# piano.net
KiCad netlist of a schematic drawn in EAGLE
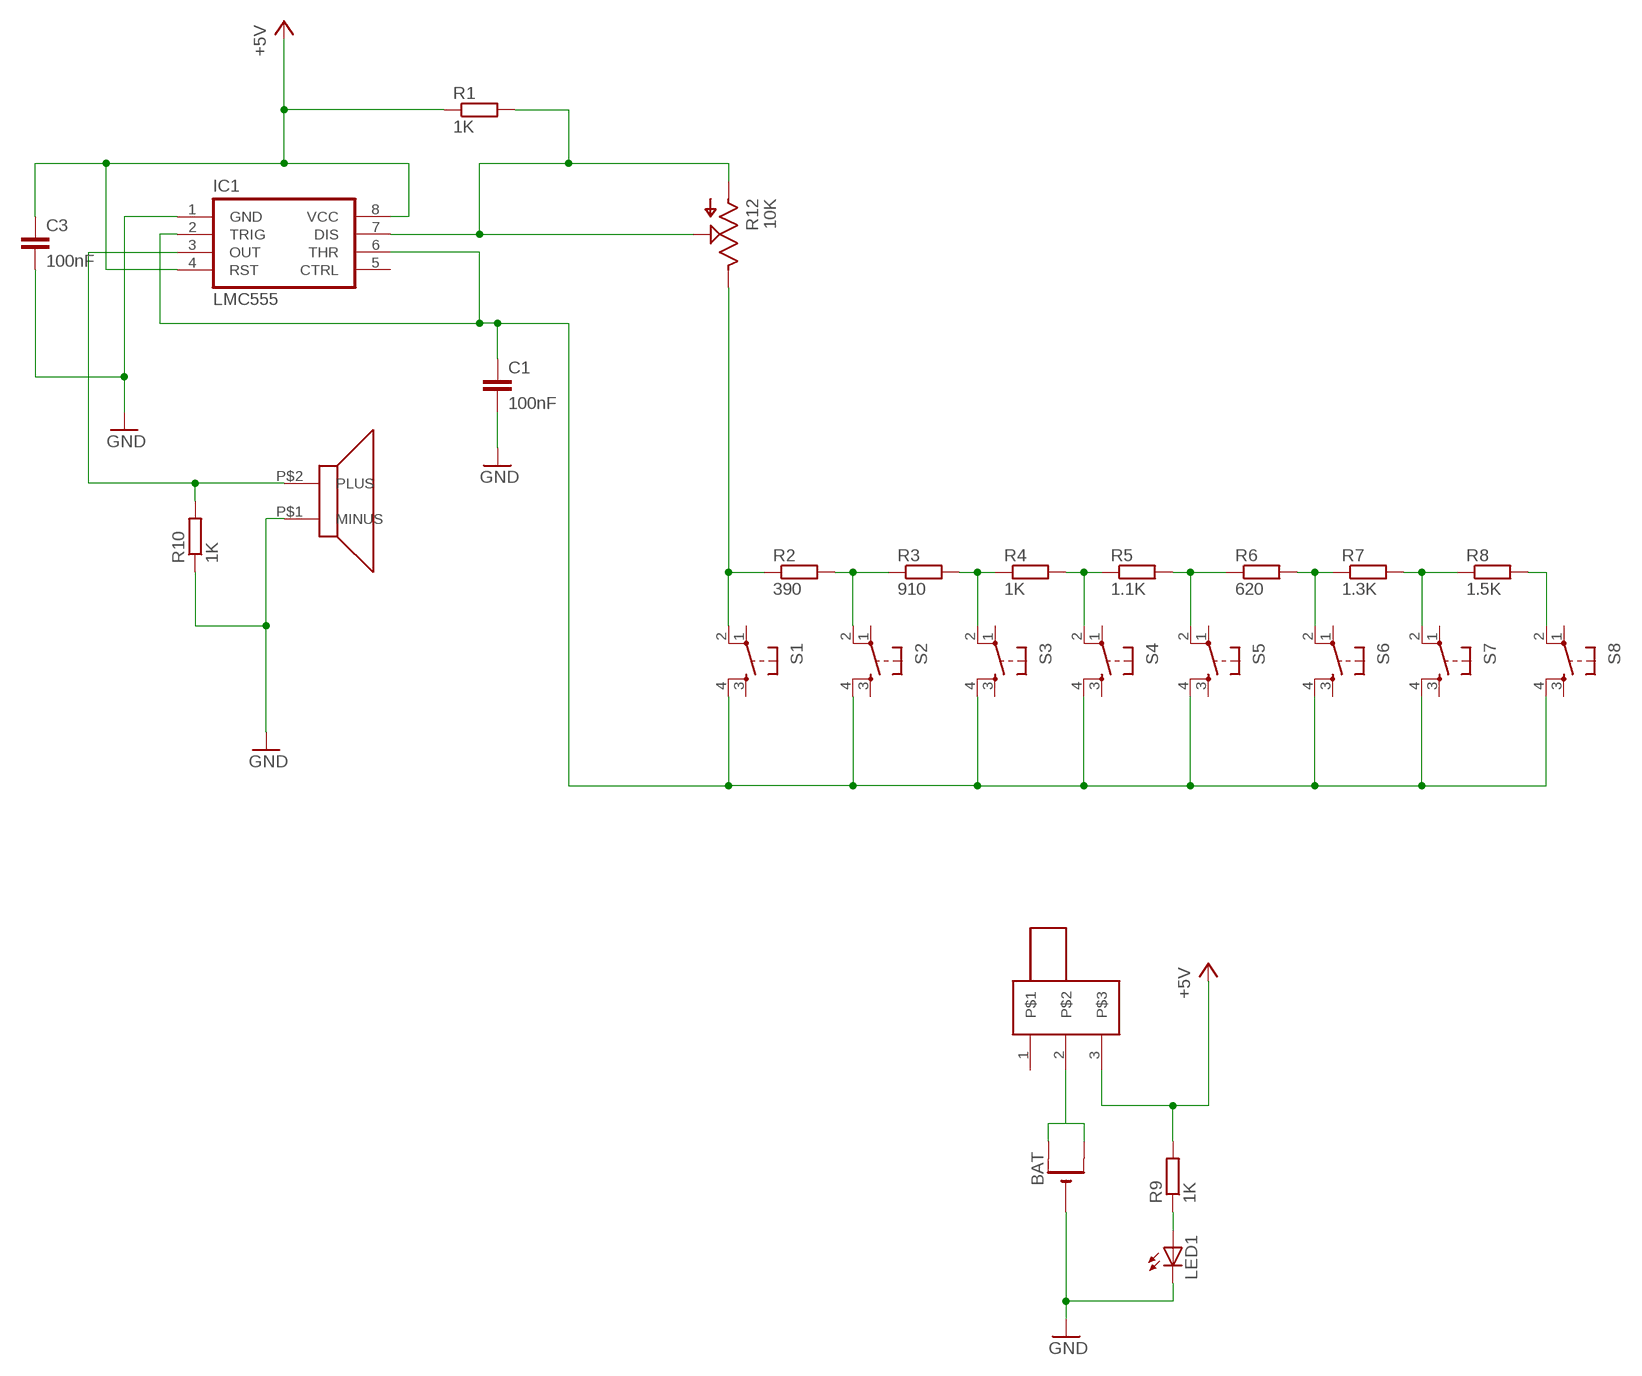
[diagram p0: schematic, sheet 1]

(export (version "E")
  (design (tool "Eeschema 10.0.6"))
  (components
    (comp (ref "BAT")
      (value "CR1220SMT")
      (footprint "eagle-import:CR1220-SMD")
      (libsource (lib "eagle-import") (part "CR1220SMT"))
    )
    (comp (ref "C1")
      (value "100nF")
      (footprint "eagle-import:C1206")
      (libsource (lib "eagle-import") (part "C-EUC1206"))
    )
    (comp (ref "C3")
      (value "100nF")
      (footprint "eagle-import:C1206")
      (libsource (lib "eagle-import") (part "C-EUC1206"))
    )
    (comp (ref "IC1")
      (value "LMC555")
      (footprint "eagle-import:SOIC-8")
      (libsource (lib "eagle-import") (part "IC_555-SOIC8"))
    )
    (comp (ref "LED1")
      (value "LED1206")
      (footprint "eagle-import:LED-1206")
      (libsource (lib "eagle-import") (part "LED1206"))
    )
    (comp (ref "R1")
      (value "1K")
      (footprint "eagle-import:R1206")
      (libsource (lib "eagle-import") (part "R-EU_R1206"))
    )
    (comp (ref "R2")
      (value "390")
      (footprint "eagle-import:R1206")
      (libsource (lib "eagle-import") (part "R-EU_R1206"))
    )
    (comp (ref "R3")
      (value "910")
      (footprint "eagle-import:R1206")
      (libsource (lib "eagle-import") (part "R-EU_R1206"))
    )
    (comp (ref "R4")
      (value "1K")
      (footprint "eagle-import:R1206")
      (libsource (lib "eagle-import") (part "R-EU_R1206"))
    )
    (comp (ref "R5")
      (value "1.1K")
      (footprint "eagle-import:R1206")
      (libsource (lib "eagle-import") (part "R-EU_R1206"))
    )
    (comp (ref "R6")
      (value "620")
      (footprint "eagle-import:R1206")
      (libsource (lib "eagle-import") (part "R-EU_R1206"))
    )
    (comp (ref "R7")
      (value "1.3K")
      (footprint "eagle-import:R1206")
      (libsource (lib "eagle-import") (part "R-EU_R1206"))
    )
    (comp (ref "R8")
      (value "1.5K")
      (footprint "eagle-import:R1206")
      (libsource (lib "eagle-import") (part "R-EU_R1206"))
    )
    (comp (ref "R9")
      (value "1K")
      (footprint "eagle-import:R1206")
      (libsource (lib "eagle-import") (part "R-EU_R1206"))
    )
    (comp (ref "R10")
      (value "1K")
      (footprint "eagle-import:R1206")
      (libsource (lib "eagle-import") (part "R-EU_R1206"))
    )
    (comp (ref "R12")
      (value "10K")
      (footprint "eagle-import:PVZ3A")
      (libsource (lib "eagle-import") (part "PVZ3A"))
    )
    (comp (ref "S1")
      (value "TAC_SWITCHSMD")
      (footprint "eagle-import:TACTILE_SWITCH_SMD")
      (libsource (lib "eagle-import") (part "TAC_SWITCHSMD"))
    )
    (comp (ref "S2")
      (value "TAC_SWITCHSMD")
      (footprint "eagle-import:TACTILE_SWITCH_SMD")
      (libsource (lib "eagle-import") (part "TAC_SWITCHSMD"))
    )
    (comp (ref "S3")
      (value "TAC_SWITCHSMD")
      (footprint "eagle-import:TACTILE_SWITCH_SMD")
      (libsource (lib "eagle-import") (part "TAC_SWITCHSMD"))
    )
    (comp (ref "S4")
      (value "TAC_SWITCHSMD")
      (footprint "eagle-import:TACTILE_SWITCH_SMD")
      (libsource (lib "eagle-import") (part "TAC_SWITCHSMD"))
    )
    (comp (ref "S5")
      (value "TAC_SWITCHSMD")
      (footprint "eagle-import:TACTILE_SWITCH_SMD")
      (libsource (lib "eagle-import") (part "TAC_SWITCHSMD"))
    )
    (comp (ref "S6")
      (value "TAC_SWITCHSMD")
      (footprint "eagle-import:TACTILE_SWITCH_SMD")
      (libsource (lib "eagle-import") (part "TAC_SWITCHSMD"))
    )
    (comp (ref "S7")
      (value "TAC_SWITCHSMD")
      (footprint "eagle-import:TACTILE_SWITCH_SMD")
      (libsource (lib "eagle-import") (part "TAC_SWITCHSMD"))
    )
    (comp (ref "S8")
      (value "TAC_SWITCHSMD")
      (footprint "eagle-import:TACTILE_SWITCH_SMD")
      (libsource (lib "eagle-import") (part "TAC_SWITCHSMD"))
    )
    (comp (ref "U$1")
      (value "SMD-100030H-05052T")
      (footprint "eagle-import:SMD-100030H")
      (libsource (lib "eagle-import") (part "SMD-100030H-05052T"))
    )
    (comp (ref "U$2")
      (value "SK12D07VG3")
      (footprint "eagle-import:SWITCH3")
      (libsource (lib "eagle-import") (part "SWITCH3"))
    )
  )
  (nets
    (net (code "1") (name "+5V") (class "Default")
      (node (ref "C3") (pin "1") (pinfunction "1_1") (pintype "passive"))
      (node (ref "IC1") (pin "4") (pinfunction "RST_4") (pintype "input"))
      (node (ref "IC1") (pin "8") (pinfunction "VCC_8") (pintype "power_in"))
      (node (ref "R1") (pin "1") (pinfunction "1_1") (pintype "passive"))
      (node (ref "R9") (pin "2") (pinfunction "2_2") (pintype "passive"))
      (node (ref "U$2") (pin "3") (pinfunction "P$3_3") (pintype "bidirectional"))
    )
    (net (code "2") (name "/CTRL") (class "Default")
      (node (ref "IC1") (pin "5") (pinfunction "CTRL_5") (pintype "power_in"))
    )
    (net (code "3") (name "GND") (class "Default")
      (node (ref "BAT") (pin "-") (pinfunction "-_-") (pintype "passive"))
      (node (ref "C1") (pin "2") (pinfunction "2_2") (pintype "passive"))
      (node (ref "C3") (pin "2") (pinfunction "2_2") (pintype "passive"))
      (node (ref "IC1") (pin "1") (pinfunction "GND_1") (pintype "power_in"))
      (node (ref "LED1") (pin "C") (pinfunction "C_C") (pintype "passive"))
      (node (ref "R10") (pin "1") (pinfunction "1_1") (pintype "passive"))
      (node (ref "U$1") (pin "P$1") (pinfunction "MINUS_P$1") (pintype "bidirectional"))
    )
    (net (code "4") (name "Net-(BAT-+)") (class "Default")
      (node (ref "BAT") (pin "+$1") (pinfunction "+_+$1") (pintype "passive"))
      (node (ref "BAT") (pin "+$2") (pinfunction "+1_+$2") (pintype "passive"))
      (node (ref "U$2") (pin "2") (pinfunction "P$2_2") (pintype "bidirectional"))
    )
    (net (code "5") (name "Net-(IC1-DIS)") (class "Default")
      (node (ref "IC1") (pin "7") (pinfunction "DIS_7") (pintype "input"))
      (node (ref "R1") (pin "2") (pinfunction "2_2") (pintype "passive"))
      (node (ref "R12") (pin "P$1") (pinfunction "P$1_P$1") (pintype "bidirectional"))
      (node (ref "R12") (pin "P$2") (pinfunction "P$2_P$2") (pintype "bidirectional"))
    )
    (net (code "6") (name "Net-(IC1-OUT)") (class "Default")
      (node (ref "IC1") (pin "3") (pinfunction "OUT_3") (pintype "output"))
      (node (ref "R10") (pin "2") (pinfunction "2_2") (pintype "passive"))
      (node (ref "U$1") (pin "P$2") (pinfunction "PLUS_P$2") (pintype "bidirectional"))
    )
    (net (code "7") (name "Net-(IC1-THR)") (class "Default")
      (node (ref "C1") (pin "1") (pinfunction "1_1") (pintype "passive"))
      (node (ref "IC1") (pin "2") (pinfunction "TRIG_2") (pintype "input"))
      (node (ref "IC1") (pin "6") (pinfunction "THR_6") (pintype "input"))
      (node (ref "S1") (pin "4") (pinfunction "4_4") (pintype "passive"))
      (node (ref "S2") (pin "4") (pinfunction "4_4") (pintype "passive"))
      (node (ref "S3") (pin "4") (pinfunction "4_4") (pintype "passive"))
      (node (ref "S4") (pin "4") (pinfunction "4_4") (pintype "passive"))
      (node (ref "S5") (pin "4") (pinfunction "4_4") (pintype "passive"))
      (node (ref "S6") (pin "4") (pinfunction "4_4") (pintype "passive"))
      (node (ref "S7") (pin "4") (pinfunction "4_4") (pintype "passive"))
      (node (ref "S8") (pin "4") (pinfunction "4_4") (pintype "passive"))
    )
    (net (code "8") (name "Net-(LED1-PadA)") (class "Default")
      (node (ref "LED1") (pin "A") (pinfunction "A_A") (pintype "passive"))
      (node (ref "R9") (pin "1") (pinfunction "1_1") (pintype "passive"))
    )
    (net (code "9") (name "Net-(R2-Pad2)") (class "Default")
      (node (ref "R2") (pin "2") (pinfunction "2_2") (pintype "passive"))
      (node (ref "R3") (pin "1") (pinfunction "1_1") (pintype "passive"))
      (node (ref "S2") (pin "2") (pinfunction "2_2") (pintype "passive"))
    )
    (net (code "10") (name "Net-(R3-Pad2)") (class "Default")
      (node (ref "R3") (pin "2") (pinfunction "2_2") (pintype "passive"))
      (node (ref "R4") (pin "1") (pinfunction "1_1") (pintype "passive"))
      (node (ref "S3") (pin "2") (pinfunction "2_2") (pintype "passive"))
    )
    (net (code "11") (name "Net-(R4-Pad2)") (class "Default")
      (node (ref "R4") (pin "2") (pinfunction "2_2") (pintype "passive"))
      (node (ref "R5") (pin "1") (pinfunction "1_1") (pintype "passive"))
      (node (ref "S4") (pin "2") (pinfunction "2_2") (pintype "passive"))
    )
    (net (code "12") (name "Net-(R5-Pad2)") (class "Default")
      (node (ref "R5") (pin "2") (pinfunction "2_2") (pintype "passive"))
      (node (ref "R6") (pin "1") (pinfunction "1_1") (pintype "passive"))
      (node (ref "S5") (pin "2") (pinfunction "2_2") (pintype "passive"))
    )
    (net (code "13") (name "Net-(R6-Pad2)") (class "Default")
      (node (ref "R6") (pin "2") (pinfunction "2_2") (pintype "passive"))
      (node (ref "R7") (pin "1") (pinfunction "1_1") (pintype "passive"))
      (node (ref "S6") (pin "2") (pinfunction "2_2") (pintype "passive"))
    )
    (net (code "14") (name "Net-(R7-Pad2)") (class "Default")
      (node (ref "R7") (pin "2") (pinfunction "2_2") (pintype "passive"))
      (node (ref "R8") (pin "1") (pinfunction "1_1") (pintype "passive"))
      (node (ref "S7") (pin "2") (pinfunction "2_2") (pintype "passive"))
    )
    (net (code "15") (name "Net-(R8-Pad2)") (class "Default")
      (node (ref "R8") (pin "2") (pinfunction "2_2") (pintype "passive"))
      (node (ref "S8") (pin "2") (pinfunction "2_2") (pintype "passive"))
    )
    (net (code "16") (name "Net-(R12-PadP$3)") (class "Default")
      (node (ref "R12") (pin "P$3") (pinfunction "P$3_P$3") (pintype "bidirectional"))
      (node (ref "R2") (pin "1") (pinfunction "1_1") (pintype "passive"))
      (node (ref "S1") (pin "2") (pinfunction "2_2") (pintype "passive"))
    )
    (net (code "17") (name "unconnected-(S1-Pad1)") (class "Default")
      (node (ref "S1") (pin "1") (pinfunction "1_1") (pintype "passive"))
    )
    (net (code "18") (name "unconnected-(S1-Pad3)") (class "Default")
      (node (ref "S1") (pin "3") (pinfunction "3_3") (pintype "passive"))
    )
    (net (code "19") (name "unconnected-(S2-Pad1)") (class "Default")
      (node (ref "S2") (pin "1") (pinfunction "1_1") (pintype "passive"))
    )
    (net (code "20") (name "unconnected-(S2-Pad3)") (class "Default")
      (node (ref "S2") (pin "3") (pinfunction "3_3") (pintype "passive"))
    )
    (net (code "21") (name "unconnected-(S3-Pad1)") (class "Default")
      (node (ref "S3") (pin "1") (pinfunction "1_1") (pintype "passive"))
    )
    (net (code "22") (name "unconnected-(S3-Pad3)") (class "Default")
      (node (ref "S3") (pin "3") (pinfunction "3_3") (pintype "passive"))
    )
    (net (code "23") (name "unconnected-(S4-Pad1)") (class "Default")
      (node (ref "S4") (pin "1") (pinfunction "1_1") (pintype "passive"))
    )
    (net (code "24") (name "unconnected-(S4-Pad3)") (class "Default")
      (node (ref "S4") (pin "3") (pinfunction "3_3") (pintype "passive"))
    )
    (net (code "25") (name "unconnected-(S5-Pad1)") (class "Default")
      (node (ref "S5") (pin "1") (pinfunction "1_1") (pintype "passive"))
    )
    (net (code "26") (name "unconnected-(S5-Pad3)") (class "Default")
      (node (ref "S5") (pin "3") (pinfunction "3_3") (pintype "passive"))
    )
    (net (code "27") (name "unconnected-(S6-Pad1)") (class "Default")
      (node (ref "S6") (pin "1") (pinfunction "1_1") (pintype "passive"))
    )
    (net (code "28") (name "unconnected-(S6-Pad3)") (class "Default")
      (node (ref "S6") (pin "3") (pinfunction "3_3") (pintype "passive"))
    )
    (net (code "29") (name "unconnected-(S7-Pad1)") (class "Default")
      (node (ref "S7") (pin "1") (pinfunction "1_1") (pintype "passive"))
    )
    (net (code "30") (name "unconnected-(S7-Pad3)") (class "Default")
      (node (ref "S7") (pin "3") (pinfunction "3_3") (pintype "passive"))
    )
    (net (code "31") (name "unconnected-(S8-Pad1)") (class "Default")
      (node (ref "S8") (pin "1") (pinfunction "1_1") (pintype "passive"))
    )
    (net (code "32") (name "unconnected-(S8-Pad3)") (class "Default")
      (node (ref "S8") (pin "3") (pinfunction "3_3") (pintype "passive"))
    )
    (net (code "33") (name "unconnected-(U$2-P$1-Pad1)") (class "Default")
      (node (ref "U$2") (pin "1") (pinfunction "P$1_1") (pintype "bidirectional"))
    )
  )
)
